# Sheet1.net
KiCad netlist of a schematic drawn in Altium Designer
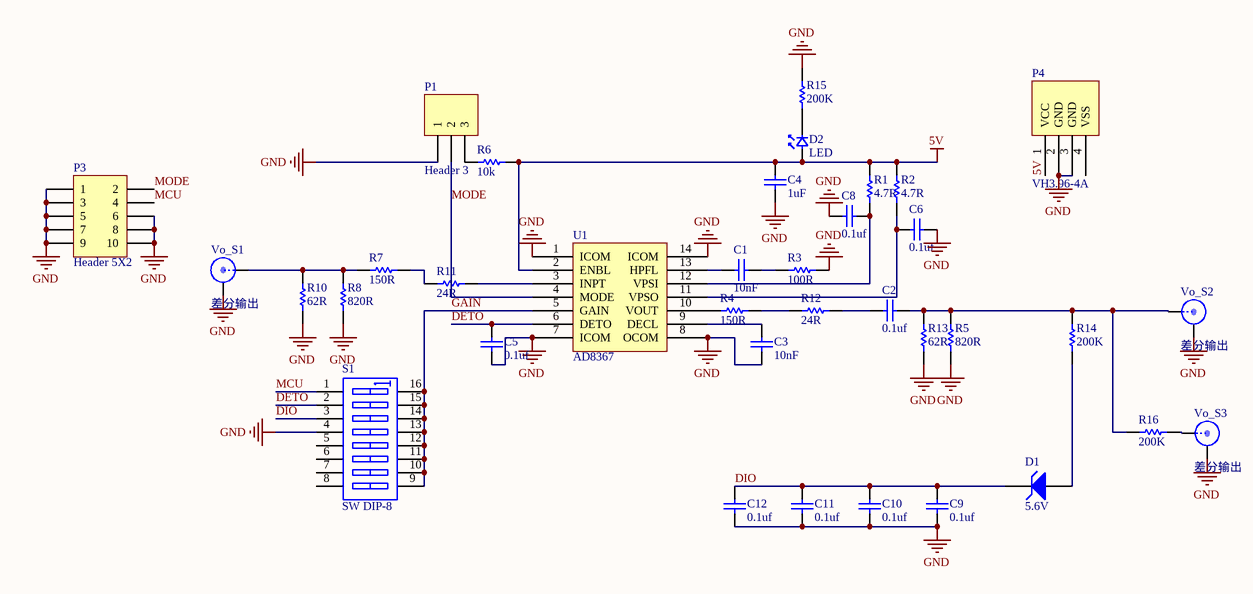
[diagram p0: Sheet1.SchDoc]

(export (version "E")
  (design (tool "Eeschema 10.0.6"))
  (components
    (comp (ref "C1") (value "10nF") (footprint "0805") (libsource (lib "Schlib1") (part "Cap")))
    (comp (ref "C2") (value "0.1uf") (footprint "0805") (libsource (lib "Schlib1") (part "Cap")))
    (comp (ref "C3") (value "10nF") (footprint "0805") (libsource (lib "Schlib1") (part "Cap")))
    (comp (ref "C4") (value "1uF") (footprint "0805") (libsource (lib "Schlib1") (part "Cap")))
    (comp (ref "C5") (value "0.1uf") (footprint "0805") (libsource (lib "Schlib1") (part "Cap")))
    (comp (ref "C6") (value "0.1uf") (footprint "0805") (libsource (lib "Schlib1") (part "Cap")))
    (comp (ref "C8") (value "0.1uf") (footprint "0805") (libsource (lib "Schlib1") (part "Cap")))
    (comp (ref "C9") (value "0.1uf") (footprint "0805") (libsource (lib "Schlib1") (part "Cap")))
    (comp (ref "C10") (value "0.1uf") (footprint "0805") (libsource (lib "Schlib1") (part "Cap")))
    (comp (ref "C11") (value "0.1uf") (footprint "0805") (libsource (lib "Schlib1") (part "Cap")))
    (comp (ref "C12") (value "0.1uf") (footprint "0805") (libsource (lib "Schlib1") (part "Cap")))
    (comp (ref "D1") (value "5.6V") (footprint "SMA/DO-214AC") (libsource (lib "Schlib1") (part "肖特基-5.6V")))
    (comp (ref "D2") (value "LED") (footprint "0805_s") (libsource (lib "Schlib1") (part "LED")))
    (comp (ref "P1")
      (value "Header 3")
      (footprint "HDR1X3")
      (description "Header, 3-Pin")
      (fields (field (name "PUBLISHER") "Altium Limited"))
      (libsource (lib "Miscellaneous Connectors") (part "Header 3"))
    )
    (comp (ref "P3")
      (value "Header 5X2")
      (footprint "HDR2X5")
      (description "Header, 5-Pin, Dual row")
      (fields (field (name "PUBLISHER") "Altium Limited"))
      (libsource (lib "Miscellaneous Connectors") (part "Header 5X2"))
    )
    (comp (ref "P4")
      (value "VH3.96-4A")
      (footprint "VH3.96-4P")
      (libsource (lib "Schlib1") (part "VH3.96-4A"))
    )
    (comp (ref "R1") (value "4.7R") (footprint "0805") (libsource (lib "Schlib1") (part "Res")))
    (comp (ref "R2") (value "4.7R") (footprint "0805") (libsource (lib "Schlib1") (part "Res")))
    (comp (ref "R3") (value "100R") (footprint "0805") (libsource (lib "Schlib1") (part "Res")))
    (comp (ref "R4") (value "150R") (footprint "0805") (libsource (lib "Schlib1") (part "Res")))
    (comp (ref "R5") (value "820R") (footprint "0805") (libsource (lib "Schlib1") (part "Res")))
    (comp (ref "R6") (value "10k") (footprint "0805") (libsource (lib "Schlib1") (part "Res")))
    (comp (ref "R7") (value "150R") (footprint "0805") (libsource (lib "Schlib1") (part "Res")))
    (comp (ref "R8") (value "820R") (footprint "0805") (libsource (lib "Schlib1") (part "Res")))
    (comp (ref "R10") (value "62R") (footprint "0805") (libsource (lib "Schlib1") (part "Res")))
    (comp (ref "R11") (value "24R") (footprint "0805") (libsource (lib "Schlib1") (part "Res")))
    (comp (ref "R12") (value "24R") (footprint "0805") (libsource (lib "Schlib1") (part "Res")))
    (comp (ref "R13") (value "62R") (footprint "0805") (libsource (lib "Schlib1") (part "Res")))
    (comp (ref "R14") (value "200K") (footprint "0805") (libsource (lib "Schlib1") (part "Res")))
    (comp (ref "R15") (value "200K") (footprint "0805") (libsource (lib "Schlib1") (part "Res")))
    (comp (ref "R16") (value "200K") (footprint "0805") (libsource (lib "Schlib1") (part "Res")))
    (comp (ref "S1")
      (value "SW DIP-8")
      (footprint "DIP-16")
      (description "DIP Switch, 8 Position, SPST")
      (fields (field (name "PUBLISHER") "Altium Limited"))
      (libsource (lib "Miscellaneous Devices") (part "SW DIP-8"))
    )
    (comp (ref "U1") (value "AD8367") (footprint "TSSOP14_M") (libsource (lib "Schlib1") (part "AD8367")))
    (comp (ref "Vo_S1") (value "差分输出") (footprint "SMA-LYING") (libsource (lib "Schlib1") (part "SMA")))
    (comp (ref "Vo_S2") (value "差分输出") (footprint "SMA-LYING") (libsource (lib "Schlib1") (part "SMA")))
    (comp (ref "Vo_S3") (value "差分输出") (footprint "SMA-LYING") (libsource (lib "Schlib1") (part "SMA")))
  )
  (nets
    (net (code "1") (name "/DETO") (class "Default")
      (node (ref "C5") (pin "2") (pinfunction "2_2") (pintype "passive"))
      (node (ref "S1") (pin "2") (pinfunction "A2_2") (pintype "passive"))
      (node (ref "U1") (pin "6") (pinfunction "DETO_6") (pintype "passive"))
    )
    (net (code "2") (name "/DIO") (class "Default")
      (node (ref "C10") (pin "2") (pinfunction "2_2") (pintype "passive"))
      (node (ref "C11") (pin "1") (pinfunction "1_1") (pintype "passive"))
      (node (ref "C12") (pin "1") (pinfunction "1_1") (pintype "passive"))
      (node (ref "C9") (pin "2") (pinfunction "2_2") (pintype "passive"))
      (node (ref "D1") (pin "2") (pinfunction "K_2") (pintype "passive"))
      (node (ref "S1") (pin "3") (pinfunction "A3_3") (pintype "passive"))
    )
    (net (code "3") (name "/GAIN") (class "Default")
      (node (ref "S1") (pin "10") (pinfunction "B7_10") (pintype "passive"))
      (node (ref "S1") (pin "11") (pinfunction "B6_11") (pintype "passive"))
      (node (ref "S1") (pin "12") (pinfunction "B5_12") (pintype "passive"))
      (node (ref "S1") (pin "13") (pinfunction "B4_13") (pintype "passive"))
      (node (ref "S1") (pin "14") (pinfunction "B3_14") (pintype "passive"))
      (node (ref "S1") (pin "15") (pinfunction "B2_15") (pintype "passive"))
      (node (ref "S1") (pin "16") (pinfunction "B1_16") (pintype "passive"))
      (node (ref "S1") (pin "9") (pinfunction "B8_9") (pintype "passive"))
      (node (ref "U1") (pin "5") (pinfunction "GAIN_5") (pintype "passive"))
    )
    (net (code "4") (name "/MCU") (class "Default")
      (node (ref "P3") (pin "4") (pinfunction "4_4") (pintype "passive"))
      (node (ref "S1") (pin "1") (pinfunction "A1_1") (pintype "passive"))
    )
    (net (code "5") (name "/MODE") (class "Default")
      (node (ref "P1") (pin "2") (pinfunction "2_2") (pintype "passive"))
      (node (ref "P3") (pin "2") (pinfunction "2_2") (pintype "passive"))
      (node (ref "U1") (pin "4") (pinfunction "MODE_4") (pintype "passive"))
    )
    (net (code "6") (name "5V") (class "Default")
      (node (ref "C4") (pin "2") (pinfunction "2_2") (pintype "passive"))
      (node (ref "D2") (pin "2") (pinfunction "2_2") (pintype "passive"))
      (node (ref "P4") (pin "1") (pinfunction "VCC_1") (pintype "passive"))
      (node (ref "R1") (pin "2") (pinfunction "2_2") (pintype "passive"))
      (node (ref "R2") (pin "2") (pinfunction "2_2") (pintype "passive"))
      (node (ref "R6") (pin "1") (pinfunction "1_1") (pintype "passive"))
      (node (ref "U1") (pin "2") (pinfunction "ENBL_2") (pintype "passive"))
    )
    (net (code "7") (name "GND") (class "Default")
      (node (ref "C10") (pin "1") (pinfunction "1_1") (pintype "passive"))
      (node (ref "C11") (pin "2") (pinfunction "2_2") (pintype "passive"))
      (node (ref "C12") (pin "2") (pinfunction "2_2") (pintype "passive"))
      (node (ref "C3") (pin "1") (pinfunction "1_1") (pintype "passive"))
      (node (ref "C4") (pin "1") (pinfunction "1_1") (pintype "passive"))
      (node (ref "C5") (pin "1") (pinfunction "1_1") (pintype "passive"))
      (node (ref "C6") (pin "1") (pinfunction "1_1") (pintype "passive"))
      (node (ref "C8") (pin "1") (pinfunction "1_1") (pintype "passive"))
      (node (ref "C9") (pin "1") (pinfunction "1_1") (pintype "passive"))
      (node (ref "P1") (pin "1") (pinfunction "1_1") (pintype "passive"))
      (node (ref "P3") (pin "1") (pinfunction "1_1") (pintype "passive"))
      (node (ref "P3") (pin "10") (pinfunction "10_10") (pintype "passive"))
      (node (ref "P3") (pin "3") (pinfunction "3_3") (pintype "passive"))
      (node (ref "P3") (pin "5") (pinfunction "5_5") (pintype "passive"))
      (node (ref "P3") (pin "6") (pinfunction "6_6") (pintype "passive"))
      (node (ref "P3") (pin "7") (pinfunction "7_7") (pintype "passive"))
      (node (ref "P3") (pin "8") (pinfunction "8_8") (pintype "passive"))
      (node (ref "P3") (pin "9") (pinfunction "9_9") (pintype "passive"))
      (node (ref "P4") (pin "2") (pinfunction "GND_2") (pintype "passive"))
      (node (ref "P4") (pin "3") (pinfunction "GND_3") (pintype "passive"))
      (node (ref "R10") (pin "1") (pinfunction "1_1") (pintype "passive"))
      (node (ref "R13") (pin "1") (pinfunction "1_1") (pintype "passive"))
      (node (ref "R15") (pin "2") (pinfunction "2_2") (pintype "passive"))
      (node (ref "R3") (pin "1") (pinfunction "1_1") (pintype "passive"))
      (node (ref "R5") (pin "1") (pinfunction "1_1") (pintype "passive"))
      (node (ref "R8") (pin "1") (pinfunction "1_1") (pintype "passive"))
      (node (ref "S1") (pin "4") (pinfunction "A4_4") (pintype "passive"))
      (node (ref "U1") (pin "1") (pinfunction "ICOM_1") (pintype "passive"))
      (node (ref "U1") (pin "14") (pinfunction "ICOM_14") (pintype "passive"))
      (node (ref "U1") (pin "7") (pinfunction "ICOM_7") (pintype "passive"))
      (node (ref "U1") (pin "8") (pinfunction "OCOM_8") (pintype "passive"))
      (node (ref "Vo_S1") (pin "1") (pinfunction "1_1") (pintype "passive"))
      (node (ref "Vo_S2") (pin "1") (pinfunction "1_1") (pintype "passive"))
      (node (ref "Vo_S3") (pin "1") (pinfunction "1_1") (pintype "passive"))
    )
    (net (code "8") (name "Net-(C1-Pad1)") (class "Default")
      (node (ref "C1") (pin "1") (pinfunction "1_1") (pintype "passive"))
      (node (ref "R3") (pin "2") (pinfunction "2_2") (pintype "passive"))
    )
    (net (code "9") (name "Net-(C2-Pad1)") (class "Default")
      (node (ref "C2") (pin "1") (pinfunction "1_1") (pintype "passive"))
      (node (ref "R13") (pin "2") (pinfunction "2_2") (pintype "passive"))
      (node (ref "R14") (pin "2") (pinfunction "2_2") (pintype "passive"))
      (node (ref "R16") (pin "1") (pinfunction "1_1") (pintype "passive"))
      (node (ref "R5") (pin "2") (pinfunction "2_2") (pintype "passive"))
      (node (ref "Vo_S2") (pin "0") (pinfunction "0_0") (pintype "passive"))
    )
    (net (code "10") (name "Net-(C2-Pad2)") (class "Default")
      (node (ref "C2") (pin "2") (pinfunction "2_2") (pintype "passive"))
      (node (ref "R12") (pin "2") (pinfunction "2_2") (pintype "passive"))
    )
    (net (code "11") (name "Net-(D1-A)") (class "Default")
      (node (ref "D1") (pin "1") (pinfunction "A_1") (pintype "passive"))
      (node (ref "R14") (pin "1") (pinfunction "1_1") (pintype "passive"))
    )
    (net (code "12") (name "Net-(D2-Pad1)") (class "Default")
      (node (ref "D2") (pin "1") (pinfunction "1_1") (pintype "passive"))
      (node (ref "R15") (pin "1") (pinfunction "1_1") (pintype "passive"))
    )
    (net (code "13") (name "Net-(P1-Pad3)") (class "Default")
      (node (ref "P1") (pin "3") (pinfunction "3_3") (pintype "passive"))
      (node (ref "R6") (pin "2") (pinfunction "2_2") (pintype "passive"))
    )
    (net (code "14") (name "Net-(R10-Pad2)") (class "Default")
      (node (ref "R10") (pin "2") (pinfunction "2_2") (pintype "passive"))
      (node (ref "R7") (pin "2") (pinfunction "2_2") (pintype "passive"))
      (node (ref "R8") (pin "2") (pinfunction "2_2") (pintype "passive"))
      (node (ref "Vo_S1") (pin "0") (pinfunction "0_0") (pintype "passive"))
    )
    (net (code "15") (name "Net-(R11-Pad1)") (class "Default")
      (node (ref "R11") (pin "1") (pinfunction "1_1") (pintype "passive"))
      (node (ref "R7") (pin "1") (pinfunction "1_1") (pintype "passive"))
    )
    (net (code "16") (name "Net-(R12-Pad1)") (class "Default")
      (node (ref "R12") (pin "1") (pinfunction "1_1") (pintype "passive"))
      (node (ref "R4") (pin "1") (pinfunction "1_1") (pintype "passive"))
    )
    (net (code "17") (name "Net-(R16-Pad2)") (class "Default")
      (node (ref "R16") (pin "2") (pinfunction "2_2") (pintype "passive"))
      (node (ref "Vo_S3") (pin "0") (pinfunction "0_0") (pintype "passive"))
    )
    (net (code "18") (name "Net-(U1-DECL)") (class "Default")
      (node (ref "C3") (pin "2") (pinfunction "2_2") (pintype "passive"))
      (node (ref "U1") (pin "9") (pinfunction "DECL_9") (pintype "passive"))
    )
    (net (code "19") (name "Net-(U1-HPFL)") (class "Default")
      (node (ref "C1") (pin "2") (pinfunction "2_2") (pintype "passive"))
      (node (ref "U1") (pin "13") (pinfunction "HPFL_13") (pintype "passive"))
    )
    (net (code "20") (name "Net-(U1-INPT)") (class "Default")
      (node (ref "R11") (pin "2") (pinfunction "2_2") (pintype "passive"))
      (node (ref "U1") (pin "3") (pinfunction "INPT_3") (pintype "passive"))
    )
    (net (code "21") (name "Net-(U1-VOUT)") (class "Default")
      (node (ref "R4") (pin "2") (pinfunction "2_2") (pintype "passive"))
      (node (ref "U1") (pin "10") (pinfunction "VOUT_10") (pintype "passive"))
    )
    (net (code "22") (name "Net-(U1-VPSI)") (class "Default")
      (node (ref "C8") (pin "2") (pinfunction "2_2") (pintype "passive"))
      (node (ref "R1") (pin "1") (pinfunction "1_1") (pintype "passive"))
      (node (ref "U1") (pin "12") (pinfunction "VPSI_12") (pintype "passive"))
    )
    (net (code "23") (name "Net-(U1-VPSO)") (class "Default")
      (node (ref "C6") (pin "2") (pinfunction "2_2") (pintype "passive"))
      (node (ref "R2") (pin "1") (pinfunction "1_1") (pintype "passive"))
      (node (ref "U1") (pin "11") (pinfunction "VPSO_11") (pintype "passive"))
    )
    (net (code "24") (name "unconnected-(P4-VSS-Pad4)") (class "Default")
      (node (ref "P4") (pin "4") (pinfunction "VSS_4") (pintype "passive"))
    )
    (net (code "25") (name "unconnected-(S1-A5-Pad5)") (class "Default")
      (node (ref "S1") (pin "5") (pinfunction "A5_5") (pintype "passive"))
    )
    (net (code "26") (name "unconnected-(S1-A6-Pad6)") (class "Default")
      (node (ref "S1") (pin "6") (pinfunction "A6_6") (pintype "passive"))
    )
    (net (code "27") (name "unconnected-(S1-A7-Pad7)") (class "Default")
      (node (ref "S1") (pin "7") (pinfunction "A7_7") (pintype "passive"))
    )
    (net (code "28") (name "unconnected-(S1-A8-Pad8)") (class "Default")
      (node (ref "S1") (pin "8") (pinfunction "A8_8") (pintype "passive"))
    )
  )
)
